# PillEndo-MkI_BATT2.net
KiCad netlist of a schematic drawn in EAGLE
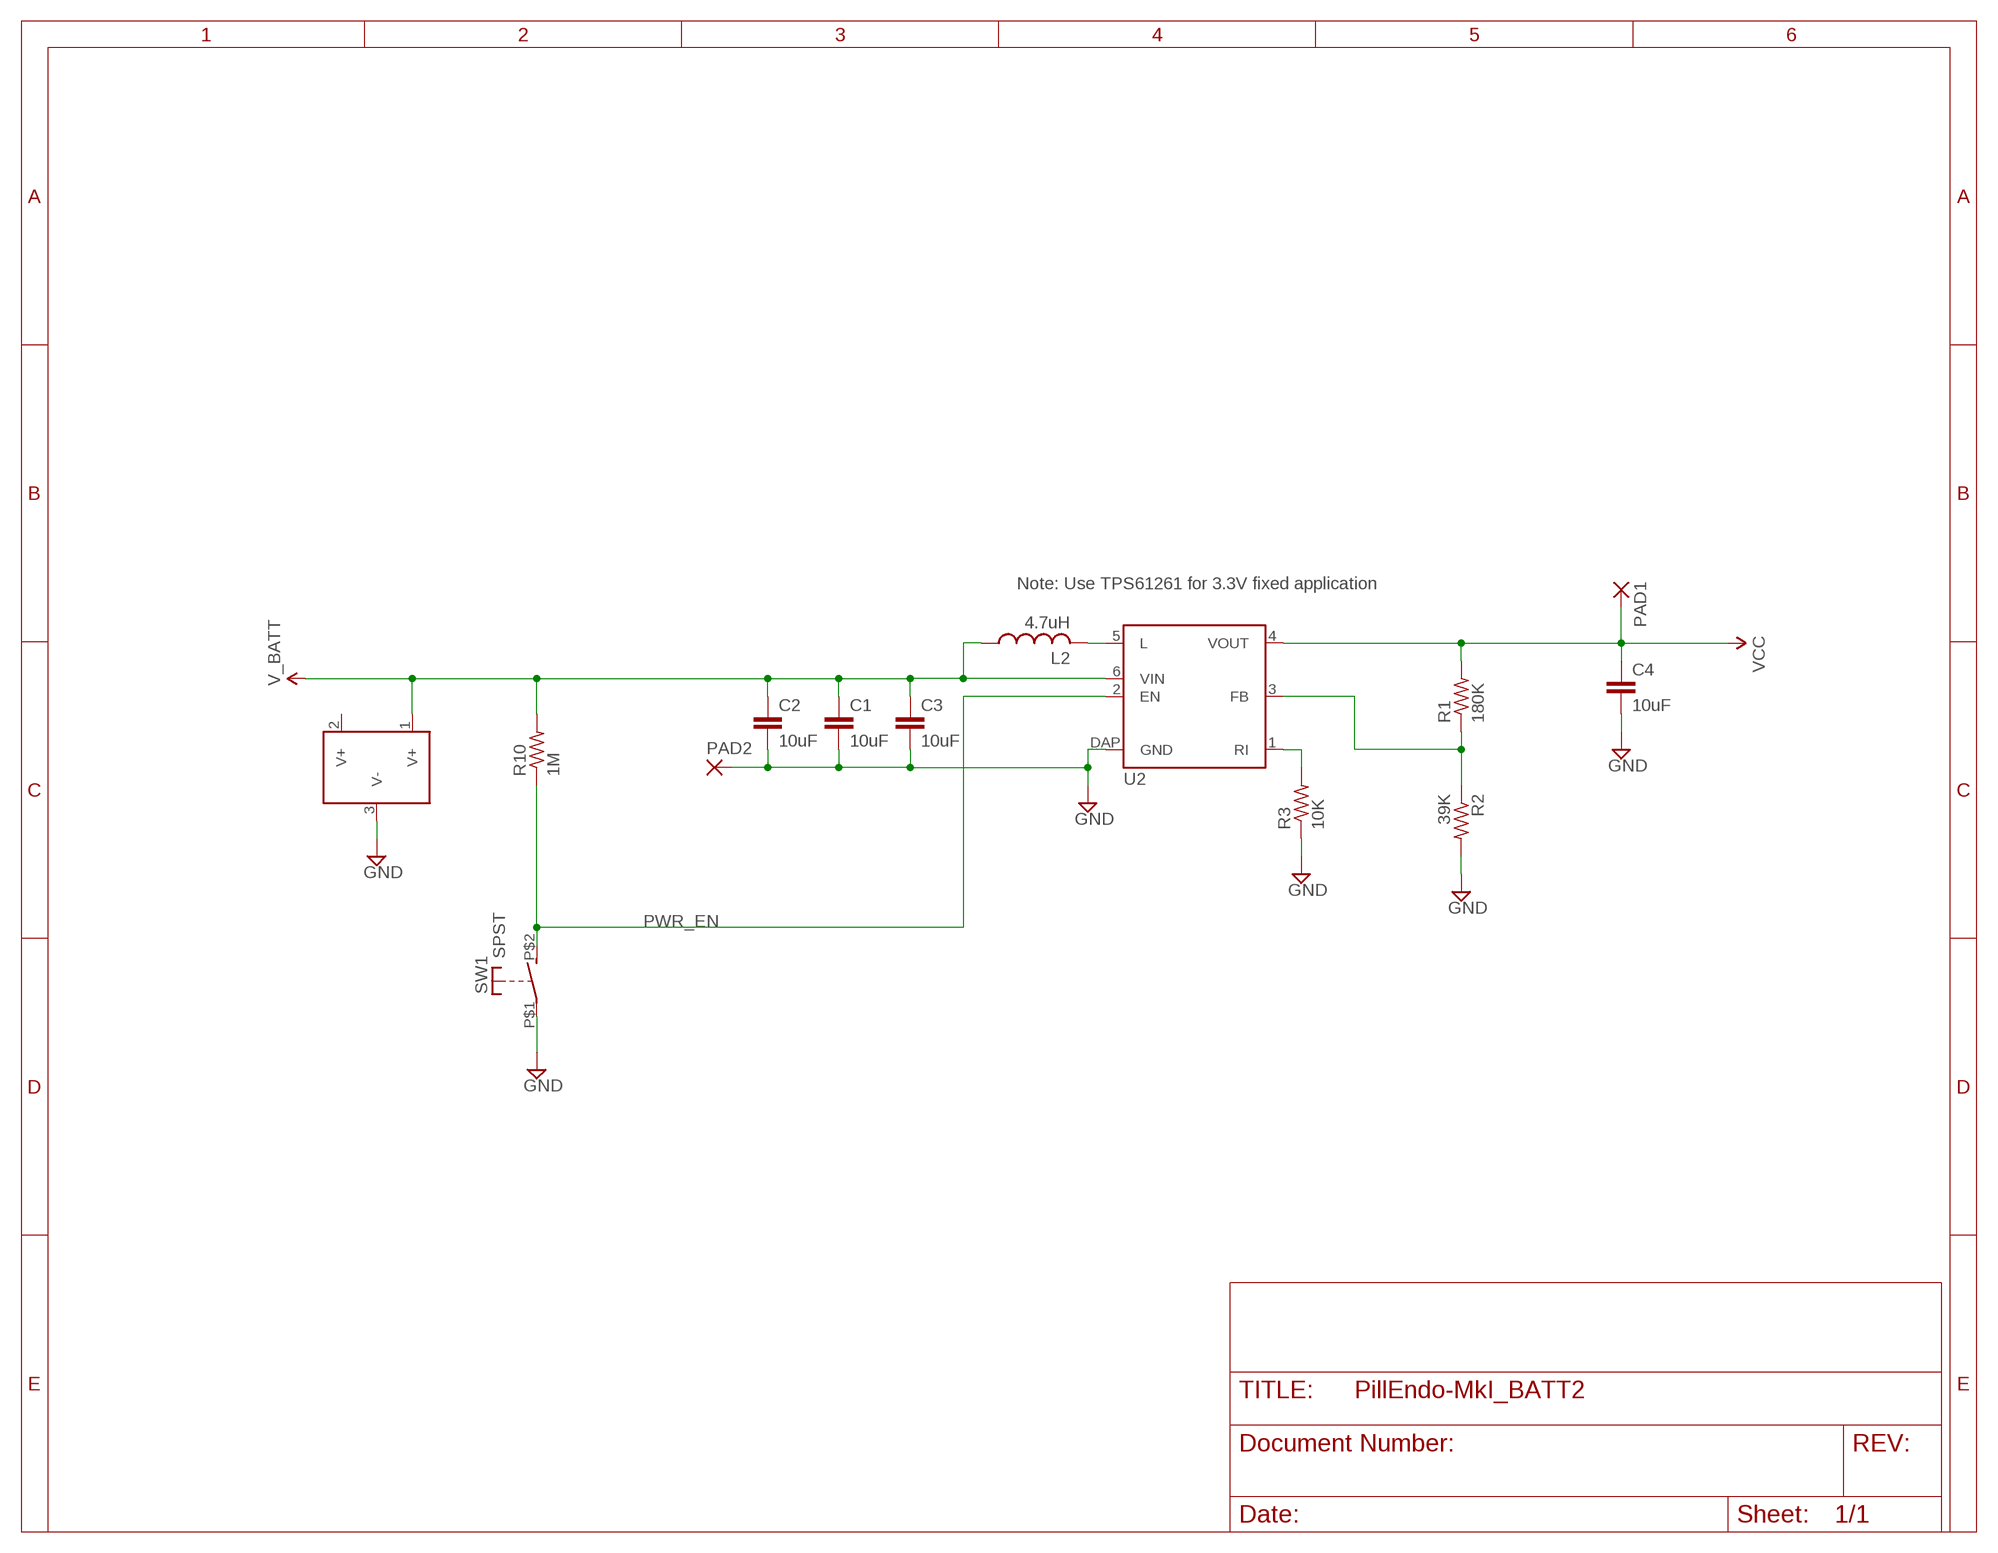
[diagram p0: schematic, sheet 1]

(export (version "E")
  (design (tool "Eeschema 10.0.6"))
  (components
    (comp (ref "C1")
      (value "10uF")
      (footprint "eagle-import:C0603")
      (libsource (lib "eagle-import") (part "C0603"))
    )
    (comp (ref "C2")
      (value "10uF")
      (footprint "eagle-import:C0603")
      (libsource (lib "eagle-import") (part "C0603"))
    )
    (comp (ref "C3")
      (value "10uF")
      (footprint "eagle-import:C0603")
      (libsource (lib "eagle-import") (part "C0603"))
    )
    (comp (ref "C4")
      (value "10uF")
      (footprint "eagle-import:C0603")
      (libsource (lib "eagle-import") (part "C0603"))
    )
    (comp (ref "J1")
      (value "BATT_7.9MM_TH")
      (footprint "eagle-import:BATT_CLIP_7.9MM_TH")
      (libsource (lib "eagle-import") (part "BATT_7.9MM_TH"))
    )
    (comp (ref "L2")
      (value "4.7uH")
      (footprint "eagle-import:L0603")
      (libsource (lib "eagle-import") (part "L0603"))
    )
    (comp (ref "PAD1")
      (value "SMD2")
      (footprint "eagle-import:SMD1,27-2,54")
      (libsource (lib "eagle-import") (part "SMD2"))
    )
    (comp (ref "PAD2")
      (value "SMD2")
      (footprint "eagle-import:SMD1,27-2,54")
      (libsource (lib "eagle-import") (part "SMD2"))
    )
    (comp (ref "R1")
      (value "180K")
      (footprint "eagle-import:R0402")
      (libsource (lib "eagle-import") (part "R0402"))
    )
    (comp (ref "R2")
      (value "39K")
      (footprint "eagle-import:R0402")
      (libsource (lib "eagle-import") (part "R0402"))
    )
    (comp (ref "R3")
      (value "10K")
      (footprint "eagle-import:R0402")
      (libsource (lib "eagle-import") (part "R0402"))
    )
    (comp (ref "R10")
      (value "1M")
      (footprint "eagle-import:R0402")
      (libsource (lib "eagle-import") (part "R0402"))
    )
    (comp (ref "SW1")
      (value "SPST")
      (footprint "eagle-import:CT05")
      (libsource (lib "eagle-import") (part "SPST"))
    )
    (comp (ref "U2")
      (value "TPS61260")
      (footprint "eagle-import:S-PWSON-N6")
      (libsource (lib "eagle-import") (part "TPS61260"))
    )
  )
  (nets
    (net (code "1") (name "/PWR_EN") (class "Default")
      (node (ref "R10") (pin "1") (pinfunction "1_1") (pintype "passive"))
      (node (ref "SW1") (pin "P$2") (pinfunction "S_P$2") (pintype "passive"))
      (node (ref "U2") (pin "2") (pinfunction "EN_2") (pintype "input"))
    )
    (net (code "2") (name "GND") (class "Default")
      (node (ref "C1") (pin "2") (pinfunction "2_2") (pintype "passive"))
      (node (ref "C2") (pin "2") (pinfunction "2_2") (pintype "passive"))
      (node (ref "C3") (pin "2") (pinfunction "2_2") (pintype "passive"))
      (node (ref "C4") (pin "2") (pinfunction "2_2") (pintype "passive"))
      (node (ref "J1") (pin "3") (pinfunction "V-_3") (pintype "bidirectional"))
      (node (ref "PAD2") (pin "1") (pinfunction "P_1") (pintype "passive"))
      (node (ref "R2") (pin "2") (pinfunction "2_2") (pintype "passive"))
      (node (ref "R3") (pin "1") (pinfunction "1_1") (pintype "passive"))
      (node (ref "SW1") (pin "P$1") (pinfunction "P_P$1") (pintype "passive"))
      (node (ref "U2") (pin "DAP") (pinfunction "GND_DAP") (pintype "power_in"))
    )
    (net (code "3") (name "Net-(U2-FB)") (class "Default")
      (node (ref "R1") (pin "1") (pinfunction "1_1") (pintype "passive"))
      (node (ref "R2") (pin "1") (pinfunction "1_1") (pintype "passive"))
      (node (ref "U2") (pin "3") (pinfunction "FB_3") (pintype "passive"))
    )
    (net (code "4") (name "Net-(U2-L)") (class "Default")
      (node (ref "L2") (pin "2") (pinfunction "2_2") (pintype "passive"))
      (node (ref "U2") (pin "5") (pinfunction "L_5") (pintype "passive"))
    )
    (net (code "5") (name "Net-(U2-RI)") (class "Default")
      (node (ref "R3") (pin "2") (pinfunction "2_2") (pintype "passive"))
      (node (ref "U2") (pin "1") (pinfunction "RI_1") (pintype "passive"))
    )
    (net (code "6") (name "VCC") (class "Default")
      (node (ref "C4") (pin "1") (pinfunction "1_1") (pintype "passive"))
      (node (ref "PAD1") (pin "1") (pinfunction "P_1") (pintype "passive"))
      (node (ref "R1") (pin "2") (pinfunction "2_2") (pintype "passive"))
      (node (ref "U2") (pin "4") (pinfunction "VOUT_4") (pintype "power_in"))
    )
    (net (code "7") (name "V_BATT") (class "Default")
      (node (ref "C1") (pin "1") (pinfunction "1_1") (pintype "passive"))
      (node (ref "C2") (pin "1") (pinfunction "1_1") (pintype "passive"))
      (node (ref "C3") (pin "1") (pinfunction "1_1") (pintype "passive"))
      (node (ref "J1") (pin "1") (pinfunction "V+_1") (pintype "bidirectional"))
      (node (ref "L2") (pin "1") (pinfunction "1_1") (pintype "passive"))
      (node (ref "R10") (pin "2") (pinfunction "2_2") (pintype "passive"))
      (node (ref "U2") (pin "6") (pinfunction "VIN_6") (pintype "power_in"))
    )
    (net (code "8") (name "unconnected-(J1-V+-Pad2)") (class "Default")
      (node (ref "J1") (pin "2") (pinfunction "V+_2") (pintype "bidirectional"))
    )
  )
)
